# Cherry-MX-Testboard.net
KiCad netlist of a schematic drawn in EAGLE
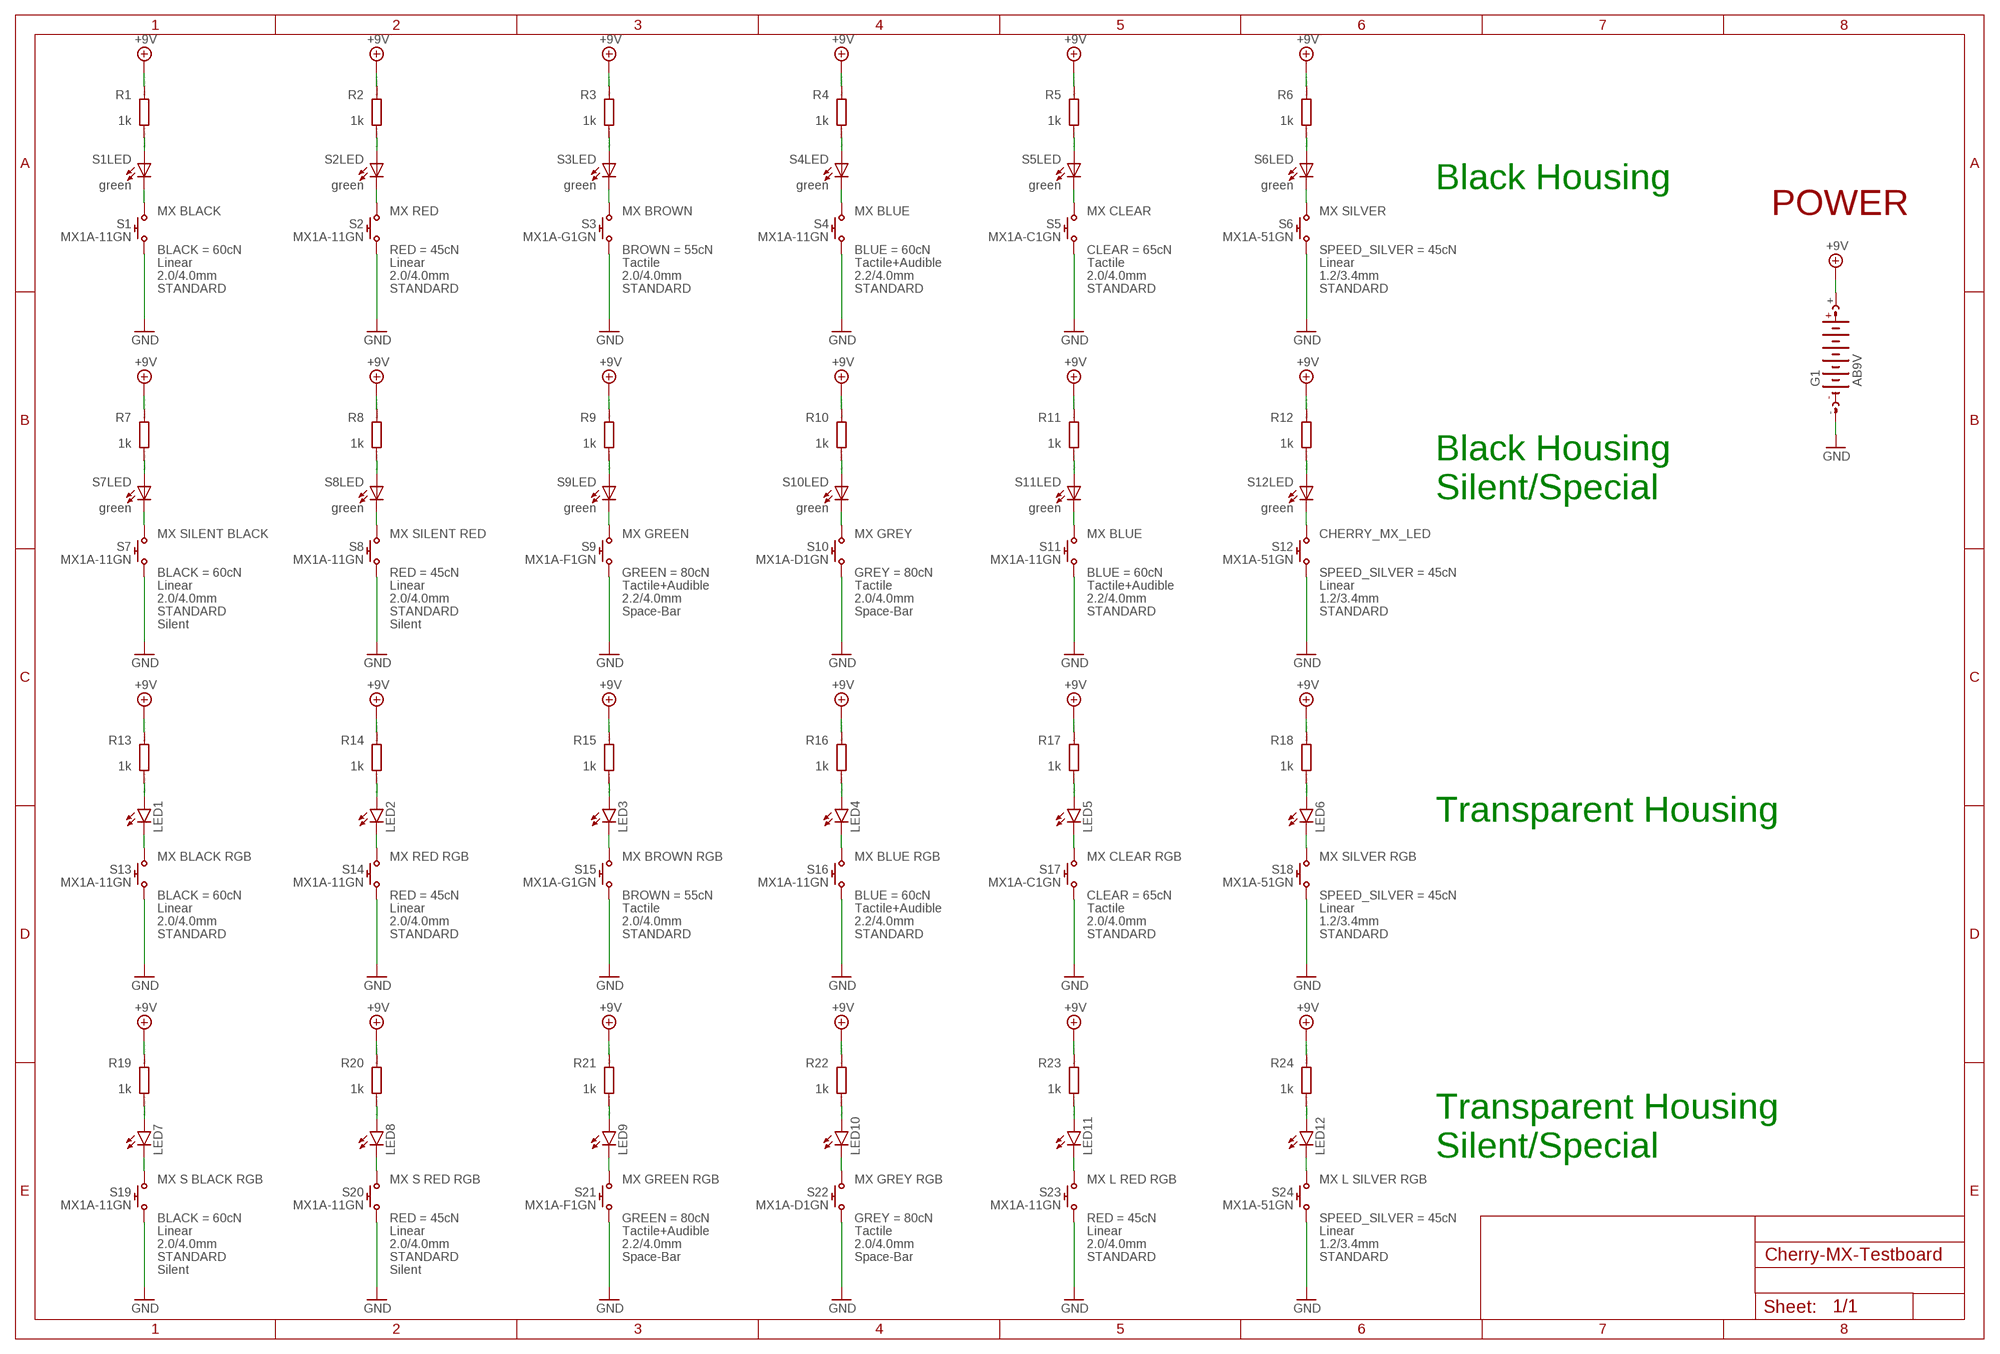
[diagram p0: schematic, sheet 1]

(export (version "E")
  (design (tool "Eeschema 10.0.6"))
  (components
    (comp (ref "G1")
      (value "AB9V")
      (footprint "eagle-import:AB9V")
      (libsource (lib "eagle-import") (part "AB9V"))
    )
    (comp (ref "LED1")
      (value "LEDMINI-TOP")
      (footprint "eagle-import:OSRAM-MINI-TOP-LED")
      (libsource (lib "eagle-import") (part "LEDMINI-TOP"))
    )
    (comp (ref "LED2")
      (value "LEDMINI-TOP")
      (footprint "eagle-import:OSRAM-MINI-TOP-LED")
      (libsource (lib "eagle-import") (part "LEDMINI-TOP"))
    )
    (comp (ref "LED3")
      (value "LEDMINI-TOP")
      (footprint "eagle-import:OSRAM-MINI-TOP-LED")
      (libsource (lib "eagle-import") (part "LEDMINI-TOP"))
    )
    (comp (ref "LED4")
      (value "LEDMINI-TOP")
      (footprint "eagle-import:OSRAM-MINI-TOP-LED")
      (libsource (lib "eagle-import") (part "LEDMINI-TOP"))
    )
    (comp (ref "LED5")
      (value "LEDMINI-TOP")
      (footprint "eagle-import:OSRAM-MINI-TOP-LED")
      (libsource (lib "eagle-import") (part "LEDMINI-TOP"))
    )
    (comp (ref "LED6")
      (value "LEDMINI-TOP")
      (footprint "eagle-import:OSRAM-MINI-TOP-LED")
      (libsource (lib "eagle-import") (part "LEDMINI-TOP"))
    )
    (comp (ref "LED7")
      (value "LEDMINI-TOP")
      (footprint "eagle-import:OSRAM-MINI-TOP-LED")
      (libsource (lib "eagle-import") (part "LEDMINI-TOP"))
    )
    (comp (ref "LED8")
      (value "LEDMINI-TOP")
      (footprint "eagle-import:OSRAM-MINI-TOP-LED")
      (libsource (lib "eagle-import") (part "LEDMINI-TOP"))
    )
    (comp (ref "LED9")
      (value "LEDMINI-TOP")
      (footprint "eagle-import:OSRAM-MINI-TOP-LED")
      (libsource (lib "eagle-import") (part "LEDMINI-TOP"))
    )
    (comp (ref "LED10")
      (value "LEDMINI-TOP")
      (footprint "eagle-import:OSRAM-MINI-TOP-LED")
      (libsource (lib "eagle-import") (part "LEDMINI-TOP"))
    )
    (comp (ref "LED11")
      (value "LEDMINI-TOP")
      (footprint "eagle-import:OSRAM-MINI-TOP-LED")
      (libsource (lib "eagle-import") (part "LEDMINI-TOP"))
    )
    (comp (ref "LED12")
      (value "LEDMINI-TOP")
      (footprint "eagle-import:OSRAM-MINI-TOP-LED")
      (libsource (lib "eagle-import") (part "LEDMINI-TOP"))
    )
    (comp (ref "R1")
      (value "1k")
      (footprint "eagle-import:R0402")
      (libsource (lib "eagle-import") (part "RR0402"))
    )
    (comp (ref "R2")
      (value "1k")
      (footprint "eagle-import:R0402")
      (libsource (lib "eagle-import") (part "RR0402"))
    )
    (comp (ref "R3")
      (value "1k")
      (footprint "eagle-import:R0402")
      (libsource (lib "eagle-import") (part "RR0402"))
    )
    (comp (ref "R4")
      (value "1k")
      (footprint "eagle-import:R0402")
      (libsource (lib "eagle-import") (part "RR0402"))
    )
    (comp (ref "R5")
      (value "1k")
      (footprint "eagle-import:R0402")
      (libsource (lib "eagle-import") (part "RR0402"))
    )
    (comp (ref "R6")
      (value "1k")
      (footprint "eagle-import:R0402")
      (libsource (lib "eagle-import") (part "RR0402"))
    )
    (comp (ref "R7")
      (value "1k")
      (footprint "eagle-import:R0402")
      (libsource (lib "eagle-import") (part "RR0402"))
    )
    (comp (ref "R8")
      (value "1k")
      (footprint "eagle-import:R0402")
      (libsource (lib "eagle-import") (part "RR0402"))
    )
    (comp (ref "R9")
      (value "1k")
      (footprint "eagle-import:R0402")
      (libsource (lib "eagle-import") (part "RR0402"))
    )
    (comp (ref "R10")
      (value "1k")
      (footprint "eagle-import:R0402")
      (libsource (lib "eagle-import") (part "RR0402"))
    )
    (comp (ref "R11")
      (value "1k")
      (footprint "eagle-import:R0402")
      (libsource (lib "eagle-import") (part "RR0402"))
    )
    (comp (ref "R12")
      (value "1k")
      (footprint "eagle-import:R0402")
      (libsource (lib "eagle-import") (part "RR0402"))
    )
    (comp (ref "R13")
      (value "1k")
      (footprint "eagle-import:R0402")
      (libsource (lib "eagle-import") (part "RR0402"))
    )
    (comp (ref "R14")
      (value "1k")
      (footprint "eagle-import:R0402")
      (libsource (lib "eagle-import") (part "RR0402"))
    )
    (comp (ref "R15")
      (value "1k")
      (footprint "eagle-import:R0402")
      (libsource (lib "eagle-import") (part "RR0402"))
    )
    (comp (ref "R16")
      (value "1k")
      (footprint "eagle-import:R0402")
      (libsource (lib "eagle-import") (part "RR0402"))
    )
    (comp (ref "R17")
      (value "1k")
      (footprint "eagle-import:R0402")
      (libsource (lib "eagle-import") (part "RR0402"))
    )
    (comp (ref "R18")
      (value "1k")
      (footprint "eagle-import:R0402")
      (libsource (lib "eagle-import") (part "RR0402"))
    )
    (comp (ref "R19")
      (value "1k")
      (footprint "eagle-import:R0402")
      (libsource (lib "eagle-import") (part "RR0402"))
    )
    (comp (ref "R20")
      (value "1k")
      (footprint "eagle-import:R0402")
      (libsource (lib "eagle-import") (part "RR0402"))
    )
    (comp (ref "R21")
      (value "1k")
      (footprint "eagle-import:R0402")
      (libsource (lib "eagle-import") (part "RR0402"))
    )
    (comp (ref "R22")
      (value "1k")
      (footprint "eagle-import:R0402")
      (libsource (lib "eagle-import") (part "RR0402"))
    )
    (comp (ref "R23")
      (value "1k")
      (footprint "eagle-import:R0402")
      (libsource (lib "eagle-import") (part "RR0402"))
    )
    (comp (ref "R24")
      (value "1k")
      (footprint "eagle-import:R0402")
      (libsource (lib "eagle-import") (part "RR0402"))
    )
    (comp (ref "S1")
      (value "MX BLACK")
      (footprint "eagle-import:CHERRY_MX_LED")
      (fields
        (field (name "BLACK") "60cN")
        (field (name "CHARACTERISTICS") "Linear")
        (field (name "CODE") "MX1A-11GN")
        (field (name "COLOR") "green")
        (field (name "FEATURE") "STANDARD")
        (field (name "TRAVEL") "2.0/4.0mm")
      )
      (libsource (lib "eagle-import") (part "CHERRY_MX_LED"))
    )
    (comp (ref "S2")
      (value "MX RED")
      (footprint "eagle-import:CHERRY_MX_LED")
      (fields
        (field (name "CHARACTERISTICS") "Linear")
        (field (name "CODE") "MX1A-11GN")
        (field (name "COLOR") "green")
        (field (name "FEATURE") "STANDARD")
        (field (name "RED") "45cN")
        (field (name "TRAVEL") "2.0/4.0mm")
      )
      (libsource (lib "eagle-import") (part "CHERRY_MX_LED"))
    )
    (comp (ref "S3")
      (value "MX BROWN")
      (footprint "eagle-import:CHERRY_MX_LED")
      (fields
        (field (name "BROWN") "55cN")
        (field (name "CHARACTERISTICS") "Tactile")
        (field (name "CODE") "MX1A-G1GN")
        (field (name "COLOR") "green")
        (field (name "FEATURE") "STANDARD")
        (field (name "TRAVEL") "2.0/4.0mm")
      )
      (libsource (lib "eagle-import") (part "CHERRY_MX_LED"))
    )
    (comp (ref "S4")
      (value "MX BLUE")
      (footprint "eagle-import:CHERRY_MX_LED")
      (fields
        (field (name "BLUE") "60cN")
        (field (name "CHARACTERISTICS") "Tactile+Audible")
        (field (name "CODE") "MX1A-11GN")
        (field (name "COLOR") "green")
        (field (name "FEATURE") "STANDARD")
        (field (name "MOUSER") "540_MX1A_E1NW")
        (field (name "TRAVEL") "2.2/4.0mm")
      )
      (libsource (lib "eagle-import") (part "CHERRY_MX_LED"))
    )
    (comp (ref "S5")
      (value "MX CLEAR")
      (footprint "eagle-import:CHERRY_MX_LED")
      (fields
        (field (name "CHARACTERISTICS") "Tactile")
        (field (name "CLEAR") "65cN")
        (field (name "CODE") "MX1A-C1GN")
        (field (name "COLOR") "green")
        (field (name "FEATURE") "STANDARD")
        (field (name "TRAVEL") "2.0/4.0mm")
      )
      (libsource (lib "eagle-import") (part "CHERRY_MX_LED"))
    )
    (comp (ref "S6")
      (value "MX SILVER")
      (footprint "eagle-import:CHERRY_MX_LED")
      (fields
        (field (name "CHARACTERISTICS") "Linear")
        (field (name "CODE") "MX1A-51GN")
        (field (name "COLOR") "green")
        (field (name "FEATURE") "STANDARD")
        (field (name "SPEED_SILVER") "45cN")
        (field (name "TRAVEL") "1.2/3.4mm")
      )
      (libsource (lib "eagle-import") (part "CHERRY_MX_LED"))
    )
    (comp (ref "S7")
      (value "MX SILENT BLACK")
      (footprint "eagle-import:CHERRY_MX_LED")
      (fields
        (field (name "BLACK") "60cN")
        (field (name "CHARACTERISTICS") "Linear")
        (field (name "CODE") "MX1A-11GN")
        (field (name "COLOR") "green")
        (field (name "FEATURE") "STANDARD")
        (field (name "NOISE") "Silent")
        (field (name "TRAVEL") "2.0/4.0mm")
      )
      (libsource (lib "eagle-import") (part "CHERRY_MX_LED"))
    )
    (comp (ref "S8")
      (value "MX SILENT RED")
      (footprint "eagle-import:CHERRY_MX_LED")
      (fields
        (field (name "CHARACTERISTICS") "Linear")
        (field (name "CODE") "MX1A-11GN")
        (field (name "COLOR") "green")
        (field (name "FEATURE") "STANDARD")
        (field (name "NOISE") "Silent")
        (field (name "RED") "45cN")
        (field (name "TRAVEL") "2.0/4.0mm")
      )
      (libsource (lib "eagle-import") (part "CHERRY_MX_LED"))
    )
    (comp (ref "S9")
      (value "MX GREEN")
      (footprint "eagle-import:CHERRY_MX_LED")
      (fields
        (field (name "CHARACTERISTICS") "Tactile+Audible")
        (field (name "CODE") "MX1A-F1GN")
        (field (name "COLOR") "green")
        (field (name "FEATURE") "Space-Bar")
        (field (name "GREEN") "80cN")
        (field (name "TRAVEL") "2.2/4.0mm")
      )
      (libsource (lib "eagle-import") (part "CHERRY_MX_LED"))
    )
    (comp (ref "S10")
      (value "MX GREY")
      (footprint "eagle-import:CHERRY_MX_LED")
      (fields
        (field (name "CHARACTERISTICS") "Tactile")
        (field (name "CODE") "MX1A-D1GN")
        (field (name "COLOR") "green")
        (field (name "FEATURE") "Space-Bar")
        (field (name "GREY") "80cN")
        (field (name "MOUSER") "540_MX1A_21NW")
        (field (name "TRAVEL") "2.0/4.0mm")
      )
      (libsource (lib "eagle-import") (part "CHERRY_MX_LED"))
    )
    (comp (ref "S11")
      (value "MX BLUE")
      (footprint "eagle-import:CHERRY_MX_LED")
      (fields
        (field (name "BLUE") "60cN")
        (field (name "CHARACTERISTICS") "Tactile+Audible")
        (field (name "CODE") "MX1A-11GN")
        (field (name "COLOR") "green")
        (field (name "FEATURE") "STANDARD")
        (field (name "MOUSER") "540_MX1A_E1NW")
        (field (name "TRAVEL") "2.2/4.0mm")
      )
      (libsource (lib "eagle-import") (part "CHERRY_MX_LED"))
    )
    (comp (ref "S12")
      (value "CHERRY_MX_LED")
      (footprint "eagle-import:CHERRY_MX_LED")
      (fields
        (field (name "CHARACTERISTICS") "Linear")
        (field (name "CODE") "MX1A-51GN")
        (field (name "COLOR") "green")
        (field (name "FEATURE") "STANDARD")
        (field (name "SPEED_SILVER") "45cN")
        (field (name "TRAVEL") "1.2/3.4mm")
      )
      (libsource (lib "eagle-import") (part "CHERRY_MX_LED"))
    )
    (comp (ref "S13")
      (value "MX BLACK RGB")
      (footprint "eagle-import:CHERRY_MX")
      (fields
        (field (name "BLACK") "60cN")
        (field (name "CHARACTERISTICS") "Linear")
        (field (name "CODE") "MX1A-11GN")
        (field (name "COLOR") "green")
        (field (name "FEATURE") "STANDARD")
        (field (name "TRAVEL") "2.0/4.0mm")
      )
      (libsource (lib "eagle-import") (part "CHERRY_MX"))
    )
    (comp (ref "S14")
      (value "MX RED RGB")
      (footprint "eagle-import:CHERRY_MX")
      (fields
        (field (name "CHARACTERISTICS") "Linear")
        (field (name "CODE") "MX1A-11GN")
        (field (name "COLOR") "green")
        (field (name "FEATURE") "STANDARD")
        (field (name "RED") "45cN")
        (field (name "TRAVEL") "2.0/4.0mm")
      )
      (libsource (lib "eagle-import") (part "CHERRY_MX"))
    )
    (comp (ref "S15")
      (value "MX BROWN RGB")
      (footprint "eagle-import:CHERRY_MX")
      (fields
        (field (name "BROWN") "55cN")
        (field (name "CHARACTERISTICS") "Tactile")
        (field (name "CODE") "MX1A-G1GN")
        (field (name "COLOR") "green")
        (field (name "FEATURE") "STANDARD")
        (field (name "TRAVEL") "2.0/4.0mm")
      )
      (libsource (lib "eagle-import") (part "CHERRY_MX"))
    )
    (comp (ref "S16")
      (value "MX BLUE RGB")
      (footprint "eagle-import:CHERRY_MX")
      (fields
        (field (name "BLUE") "60cN")
        (field (name "CHARACTERISTICS") "Tactile+Audible")
        (field (name "CODE") "MX1A-11GN")
        (field (name "COLOR") "green")
        (field (name "FEATURE") "STANDARD")
        (field (name "TRAVEL") "2.2/4.0mm")
      )
      (libsource (lib "eagle-import") (part "CHERRY_MX"))
    )
    (comp (ref "S17")
      (value "MX CLEAR RGB")
      (footprint "eagle-import:CHERRY_MX")
      (fields
        (field (name "CHARACTERISTICS") "Tactile")
        (field (name "CLEAR") "65cN")
        (field (name "CODE") "MX1A-C1GN")
        (field (name "COLOR") "green")
        (field (name "FEATURE") "STANDARD")
        (field (name "TRAVEL") "2.0/4.0mm")
      )
      (libsource (lib "eagle-import") (part "CHERRY_MX"))
    )
    (comp (ref "S18")
      (value "MX SILVER RGB")
      (footprint "eagle-import:CHERRY_MX")
      (fields
        (field (name "CHARACTERISTICS") "Linear")
        (field (name "CODE") "MX1A-51GN")
        (field (name "COLOR") "green")
        (field (name "FEATURE") "STANDARD")
        (field (name "SPEED_SILVER") "45cN")
        (field (name "TRAVEL") "1.2/3.4mm")
      )
      (libsource (lib "eagle-import") (part "CHERRY_MX"))
    )
    (comp (ref "S19")
      (value "MX S BLACK RGB")
      (footprint "eagle-import:CHERRY_MX")
      (fields
        (field (name "BLACK") "60cN")
        (field (name "CHARACTERISTICS") "Linear")
        (field (name "CODE") "MX1A-11GN")
        (field (name "COLOR") "green")
        (field (name "FEATURE") "STANDARD")
        (field (name "NOISE") "Silent")
        (field (name "TRAVEL") "2.0/4.0mm")
      )
      (libsource (lib "eagle-import") (part "CHERRY_MX"))
    )
    (comp (ref "S20")
      (value "MX S RED RGB")
      (footprint "eagle-import:CHERRY_MX")
      (fields
        (field (name "CHARACTERISTICS") "Linear")
        (field (name "CODE") "MX1A-11GN")
        (field (name "COLOR") "green")
        (field (name "FEATURE") "STANDARD")
        (field (name "NOISE") "Silent")
        (field (name "RED") "45cN")
        (field (name "TRAVEL") "2.0/4.0mm")
      )
      (libsource (lib "eagle-import") (part "CHERRY_MX"))
    )
    (comp (ref "S21")
      (value "MX GREEN RGB")
      (footprint "eagle-import:CHERRY_MX")
      (fields
        (field (name "CHARACTERISTICS") "Tactile+Audible")
        (field (name "CODE") "MX1A-F1GN")
        (field (name "COLOR") "green")
        (field (name "FEATURE") "Space-Bar")
        (field (name "GREEN") "80cN")
        (field (name "TRAVEL") "2.2/4.0mm")
      )
      (libsource (lib "eagle-import") (part "CHERRY_MX"))
    )
    (comp (ref "S22")
      (value "MX GREY RGB")
      (footprint "eagle-import:CHERRY_MX")
      (fields
        (field (name "CHARACTERISTICS") "Tactile")
        (field (name "CODE") "MX1A-D1GN")
        (field (name "COLOR") "green")
        (field (name "FEATURE") "Space-Bar")
        (field (name "GREY") "80cN")
        (field (name "TRAVEL") "2.0/4.0mm")
      )
      (libsource (lib "eagle-import") (part "CHERRY_MX"))
    )
    (comp (ref "S23")
      (value "MX L RED RGB")
      (footprint "eagle-import:CHERRY_MX")
      (fields
        (field (name "CHARACTERISTICS") "Linear")
        (field (name "CODE") "MX1A-11GN")
        (field (name "COLOR") "green")
        (field (name "FEATURE") "STANDARD")
        (field (name "RED") "45cN")
        (field (name "TRAVEL") "2.0/4.0mm")
      )
      (libsource (lib "eagle-import") (part "CHERRY_MX"))
    )
    (comp (ref "S24")
      (value "MX L SILVER RGB")
      (footprint "eagle-import:CHERRY_MX")
      (fields
        (field (name "CHARACTERISTICS") "Linear")
        (field (name "CODE") "MX1A-51GN")
        (field (name "COLOR") "green")
        (field (name "FEATURE") "STANDARD")
        (field (name "SPEED_SILVER") "45cN")
        (field (name "TRAVEL") "1.2/3.4mm")
      )
      (libsource (lib "eagle-import") (part "CHERRY_MX"))
    )
  )
  (nets
    (net (code "1") (name "+9V") (class "Default")
      (node (ref "G1") (pin "+") (pinfunction "+_+") (pintype "passive"))
      (node (ref "R1") (pin "1") (pinfunction "1_1") (pintype "passive"))
      (node (ref "R10") (pin "1") (pinfunction "1_1") (pintype "passive"))
      (node (ref "R11") (pin "1") (pinfunction "1_1") (pintype "passive"))
      (node (ref "R12") (pin "1") (pinfunction "1_1") (pintype "passive"))
      (node (ref "R13") (pin "1") (pinfunction "1_1") (pintype "passive"))
      (node (ref "R14") (pin "1") (pinfunction "1_1") (pintype "passive"))
      (node (ref "R15") (pin "1") (pinfunction "1_1") (pintype "passive"))
      (node (ref "R16") (pin "1") (pinfunction "1_1") (pintype "passive"))
      (node (ref "R17") (pin "1") (pinfunction "1_1") (pintype "passive"))
      (node (ref "R18") (pin "1") (pinfunction "1_1") (pintype "passive"))
      (node (ref "R19") (pin "1") (pinfunction "1_1") (pintype "passive"))
      (node (ref "R2") (pin "1") (pinfunction "1_1") (pintype "passive"))
      (node (ref "R20") (pin "1") (pinfunction "1_1") (pintype "passive"))
      (node (ref "R21") (pin "1") (pinfunction "1_1") (pintype "passive"))
      (node (ref "R22") (pin "1") (pinfunction "1_1") (pintype "passive"))
      (node (ref "R23") (pin "1") (pinfunction "1_1") (pintype "passive"))
      (node (ref "R24") (pin "1") (pinfunction "1_1") (pintype "passive"))
      (node (ref "R3") (pin "1") (pinfunction "1_1") (pintype "passive"))
      (node (ref "R4") (pin "1") (pinfunction "1_1") (pintype "passive"))
      (node (ref "R5") (pin "1") (pinfunction "1_1") (pintype "passive"))
      (node (ref "R6") (pin "1") (pinfunction "1_1") (pintype "passive"))
      (node (ref "R7") (pin "1") (pinfunction "1_1") (pintype "passive"))
      (node (ref "R8") (pin "1") (pinfunction "1_1") (pintype "passive"))
      (node (ref "R9") (pin "1") (pinfunction "1_1") (pintype "passive"))
    )
    (net (code "2") (name "GND") (class "Default")
      (node (ref "G1") (pin "-") (pinfunction "-_-") (pintype "passive"))
      (node (ref "S1") (pin "S1") (pinfunction "1_S1") (pintype "passive"))
      (node (ref "S10") (pin "S1") (pinfunction "1_S1") (pintype "passive"))
      (node (ref "S11") (pin "S1") (pinfunction "1_S1") (pintype "passive"))
      (node (ref "S12") (pin "S1") (pinfunction "1_S1") (pintype "passive"))
      (node (ref "S13") (pin "S1") (pinfunction "1_S1") (pintype "passive"))
      (node (ref "S14") (pin "S1") (pinfunction "1_S1") (pintype "passive"))
      (node (ref "S15") (pin "S1") (pinfunction "1_S1") (pintype "passive"))
      (node (ref "S16") (pin "S1") (pinfunction "1_S1") (pintype "passive"))
      (node (ref "S17") (pin "S1") (pinfunction "1_S1") (pintype "passive"))
      (node (ref "S18") (pin "S1") (pinfunction "1_S1") (pintype "passive"))
      (node (ref "S19") (pin "S1") (pinfunction "1_S1") (pintype "passive"))
      (node (ref "S2") (pin "S1") (pinfunction "1_S1") (pintype "passive"))
      (node (ref "S20") (pin "S1") (pinfunction "1_S1") (pintype "passive"))
      (node (ref "S21") (pin "S1") (pinfunction "1_S1") (pintype "passive"))
      (node (ref "S22") (pin "S1") (pinfunction "1_S1") (pintype "passive"))
      (node (ref "S23") (pin "S1") (pinfunction "1_S1") (pintype "passive"))
      (node (ref "S24") (pin "S1") (pinfunction "1_S1") (pintype "passive"))
      (node (ref "S3") (pin "S1") (pinfunction "1_S1") (pintype "passive"))
      (node (ref "S4") (pin "S1") (pinfunction "1_S1") (pintype "passive"))
      (node (ref "S5") (pin "S1") (pinfunction "1_S1") (pintype "passive"))
      (node (ref "S6") (pin "S1") (pinfunction "1_S1") (pintype "passive"))
      (node (ref "S7") (pin "S1") (pinfunction "1_S1") (pintype "passive"))
      (node (ref "S8") (pin "S1") (pinfunction "1_S1") (pintype "passive"))
      (node (ref "S9") (pin "S1") (pinfunction "1_S1") (pintype "passive"))
    )
    (net (code "3") (name "Net-(LED1-PadA)") (class "Default")
      (node (ref "LED1") (pin "A") (pinfunction "A_A") (pintype "passive"))
      (node (ref "R13") (pin "2") (pinfunction "2_2") (pintype "passive"))
    )
    (net (code "4") (name "Net-(LED2-PadA)") (class "Default")
      (node (ref "LED2") (pin "A") (pinfunction "A_A") (pintype "passive"))
      (node (ref "R14") (pin "2") (pinfunction "2_2") (pintype "passive"))
    )
    (net (code "5") (name "Net-(LED3-PadA)") (class "Default")
      (node (ref "LED3") (pin "A") (pinfunction "A_A") (pintype "passive"))
      (node (ref "R15") (pin "2") (pinfunction "2_2") (pintype "passive"))
    )
    (net (code "6") (name "Net-(LED4-PadA)") (class "Default")
      (node (ref "LED4") (pin "A") (pinfunction "A_A") (pintype "passive"))
      (node (ref "R16") (pin "2") (pinfunction "2_2") (pintype "passive"))
    )
    (net (code "7") (name "Net-(LED5-PadA)") (class "Default")
      (node (ref "LED5") (pin "A") (pinfunction "A_A") (pintype "passive"))
      (node (ref "R17") (pin "2") (pinfunction "2_2") (pintype "passive"))
    )
    (net (code "8") (name "Net-(LED6-PadA)") (class "Default")
      (node (ref "LED6") (pin "A") (pinfunction "A_A") (pintype "passive"))
      (node (ref "R18") (pin "2") (pinfunction "2_2") (pintype "passive"))
    )
    (net (code "9") (name "Net-(LED7-PadA)") (class "Default")
      (node (ref "LED7") (pin "A") (pinfunction "A_A") (pintype "passive"))
      (node (ref "R19") (pin "2") (pinfunction "2_2") (pintype "passive"))
    )
    (net (code "10") (name "Net-(LED8-PadA)") (class "Default")
      (node (ref "LED8") (pin "A") (pinfunction "A_A") (pintype "passive"))
      (node (ref "R20") (pin "2") (pinfunction "2_2") (pintype "passive"))
    )
    (net (code "11") (name "Net-(LED9-PadA)") (class "Default")
      (node (ref "LED9") (pin "A") (pinfunction "A_A") (pintype "passive"))
      (node (ref "R21") (pin "2") (pinfunction "2_2") (pintype "passive"))
    )
    (net (code "12") (name "Net-(LED10-PadA)") (class "Default")
      (node (ref "LED10") (pin "A") (pinfunction "A_A") (pintype "passive"))
      (node (ref "R22") (pin "2") (pinfunction "2_2") (pintype "passive"))
    )
    (net (code "13") (name "Net-(LED11-PadA)") (class "Default")
      (node (ref "LED11") (pin "A") (pinfunction "A_A") (pintype "passive"))
      (node (ref "R23") (pin "2") (pinfunction "2_2") (pintype "passive"))
    )
    (net (code "14") (name "Net-(LED12-PadA)") (class "Default")
      (node (ref "LED12") (pin "A") (pinfunction "A_A") (pintype "passive"))
      (node (ref "R24") (pin "2") (pinfunction "2_2") (pintype "passive"))
    )
    (net (code "15") (name "Net-(S1A-2)") (class "Default")
      (node (ref "S1") (pin "L2") (pinfunction "C_L2") (pintype "passive"))
      (node (ref "S1") (pin "S2") (pinfunction "2_S2") (pintype "passive"))
    )
    (net (code "16") (name "Net-(S1B-A)") (class "Default")
      (node (ref "R1") (pin "2") (pinfunction "2_2") (pintype "passive"))
      (node (ref "S1") (pin "L1") (pinfunction "A_L1") (pintype "passive"))
    )
    (net (code "17") (name "Net-(S2A-2)") (class "Default")
      (node (ref "S2") (pin "L2") (pinfunction "C_L2") (pintype "passive"))
      (node (ref "S2") (pin "S2") (pinfunction "2_S2") (pintype "passive"))
    )
    (net (code "18") (name "Net-(S2B-A)") (class "Default")
      (node (ref "R2") (pin "2") (pinfunction "2_2") (pintype "passive"))
      (node (ref "S2") (pin "L1") (pinfunction "A_L1") (pintype "passive"))
    )
    (net (code "19") (name "Net-(S3A-2)") (class "Default")
      (node (ref "S3") (pin "L2") (pinfunction "C_L2") (pintype "passive"))
      (node (ref "S3") (pin "S2") (pinfunction "2_S2") (pintype "passive"))
    )
    (net (code "20") (name "Net-(S3B-A)") (class "Default")
      (node (ref "R3") (pin "2") (pinfunction "2_2") (pintype "passive"))
      (node (ref "S3") (pin "L1") (pinfunction "A_L1") (pintype "passive"))
    )
    (net (code "21") (name "Net-(S4A-2)") (class "Default")
      (node (ref "S4") (pin "L2") (pinfunction "C_L2") (pintype "passive"))
      (node (ref "S4") (pin "S2") (pinfunction "2_S2") (pintype "passive"))
    )
    (net (code "22") (name "Net-(S4B-A)") (class "Default")
      (node (ref "R4") (pin "2") (pinfunction "2_2") (pintype "passive"))
      (node (ref "S4") (pin "L1") (pinfunction "A_L1") (pintype "passive"))
    )
    (net (code "23") (name "Net-(S5A-2)") (class "Default")
      (node (ref "S5") (pin "L2") (pinfunction "C_L2") (pintype "passive"))
      (node (ref "S5") (pin "S2") (pinfunction "2_S2") (pintype "passive"))
    )
    (net (code "24") (name "Net-(S5B-A)") (class "Default")
      (node (ref "R5") (pin "2") (pinfunction "2_2") (pintype "passive"))
      (node (ref "S5") (pin "L1") (pinfunction "A_L1") (pintype "passive"))
    )
    (net (code "25") (name "Net-(S6A-2)") (class "Default")
      (node (ref "S6") (pin "L2") (pinfunction "C_L2") (pintype "passive"))
      (node (ref "S6") (pin "S2") (pinfunction "2_S2") (pintype "passive"))
    )
    (net (code "26") (name "Net-(S6B-A)") (class "Default")
      (node (ref "R6") (pin "2") (pinfunction "2_2") (pintype "passive"))
      (node (ref "S6") (pin "L1") (pinfunction "A_L1") (pintype "passive"))
    )
    (net (code "27") (name "Net-(S7A-2)") (class "Default")
      (node (ref "S7") (pin "L2") (pinfunction "C_L2") (pintype "passive"))
      (node (ref "S7") (pin "S2") (pinfunction "2_S2") (pintype "passive"))
    )
    (net (code "28") (name "Net-(S7B-A)") (class "Default")
      (node (ref "R7") (pin "2") (pinfunction "2_2") (pintype "passive"))
      (node (ref "S7") (pin "L1") (pinfunction "A_L1") (pintype "passive"))
    )
    (net (code "29") (name "Net-(S8A-2)") (class "Default")
      (node (ref "S8") (pin "L2") (pinfunction "C_L2") (pintype "passive"))
      (node (ref "S8") (pin "S2") (pinfunction "2_S2") (pintype "passive"))
    )
    (net (code "30") (name "Net-(S8B-A)") (class "Default")
      (node (ref "R8") (pin "2") (pinfunction "2_2") (pintype "passive"))
      (node (ref "S8") (pin "L1") (pinfunction "A_L1") (pintype "passive"))
    )
    (net (code "31") (name "Net-(S9A-2)") (class "Default")
      (node (ref "S9") (pin "L2") (pinfunction "C_L2") (pintype "passive"))
      (node (ref "S9") (pin "S2") (pinfunction "2_S2") (pintype "passive"))
    )
    (net (code "32") (name "Net-(S9B-A)") (class "Default")
      (node (ref "R9") (pin "2") (pinfunction "2_2") (pintype "passive"))
      (node (ref "S9") (pin "L1") (pinfunction "A_L1") (pintype "passive"))
    )
    (net (code "33") (name "Net-(S10A-2)") (class "Default")
      (node (ref "S10") (pin "L2") (pinfunction "C_L2") (pintype "passive"))
      (node (ref "S10") (pin "S2") (pinfunction "2_S2") (pintype "passive"))
    )
    (net (code "34") (name "Net-(S10B-A)") (class "Default")
      (node (ref "R10") (pin "2") (pinfunction "2_2") (pintype "passive"))
      (node (ref "S10") (pin "L1") (pinfunction "A_L1") (pintype "passive"))
    )
    (net (code "35") (name "Net-(S11A-2)") (class "Default")
      (node (ref "S11") (pin "L2") (pinfunction "C_L2") (pintype "passive"))
      (node (ref "S11") (pin "S2") (pinfunction "2_S2") (pintype "passive"))
    )
    (net (code "36") (name "Net-(S11B-A)") (class "Default")
      (node (ref "R11") (pin "2") (pinfunction "2_2") (pintype "passive"))
      (node (ref "S11") (pin "L1") (pinfunction "A_L1") (pintype "passive"))
    )
    (net (code "37") (name "Net-(S12A-2)") (class "Default")
      (node (ref "S12") (pin "L2") (pinfunction "C_L2") (pintype "passive"))
      (node (ref "S12") (pin "S2") (pinfunction "2_S2") (pintype "passive"))
    )
    (net (code "38") (name "Net-(S12B-A)") (class "Default")
      (node (ref "R12") (pin "2") (pinfunction "2_2") (pintype "passive"))
      (node (ref "S12") (pin "L1") (pinfunction "A_L1") (pintype "passive"))
    )
    (net (code "39") (name "Net-(S13-2)") (class "Default")
      (node (ref "LED1") (pin "C") (pinfunction "C_C") (pintype "passive"))
      (node (ref "S13") (pin "S2") (pinfunction "2_S2") (pintype "passive"))
    )
    (net (code "40") (name "Net-(S14-2)") (class "Default")
      (node (ref "LED2") (pin "C") (pinfunction "C_C") (pintype "passive"))
      (node (ref "S14") (pin "S2") (pinfunction "2_S2") (pintype "passive"))
    )
    (net (code "41") (name "Net-(S15-2)") (class "Default")
      (node (ref "LED3") (pin "C") (pinfunction "C_C") (pintype "passive"))
      (node (ref "S15") (pin "S2") (pinfunction "2_S2") (pintype "passive"))
    )
    (net (code "42") (name "Net-(S16-2)") (class "Default")
      (node (ref "LED4") (pin "C") (pinfunction "C_C") (pintype "passive"))
      (node (ref "S16") (pin "S2") (pinfunction "2_S2") (pintype "passive"))
    )
    (net (code "43") (name "Net-(S17-2)") (class "Default")
      (node (ref "LED5") (pin "C") (pinfunction "C_C") (pintype "passive"))
      (node (ref "S17") (pin "S2") (pinfunction "2_S2") (pintype "passive"))
    )
    (net (code "44") (name "Net-(S18-2)") (class "Default")
      (node (ref "LED6") (pin "C") (pinfunction "C_C") (pintype "passive"))
      (node (ref "S18") (pin "S2") (pinfunction "2_S2") (pintype "passive"))
    )
    (net (code "45") (name "Net-(S19-2)") (class "Default")
      (node (ref "LED7") (pin "C") (pinfunction "C_C") (pintype "passive"))
      (node (ref "S19") (pin "S2") (pinfunction "2_S2") (pintype "passive"))
    )
    (net (code "46") (name "Net-(S20-2)") (class "Default")
      (node (ref "LED8") (pin "C") (pinfunction "C_C") (pintype "passive"))
      (node (ref "S20") (pin "S2") (pinfunction "2_S2") (pintype "passive"))
    )
    (net (code "47") (name "Net-(S21-2)") (class "Default")
      (node (ref "LED9") (pin "C") (pinfunction "C_C") (pintype "passive"))
      (node (ref "S21") (pin "S2") (pinfunction "2_S2") (pintype "passive"))
    )
    (net (code "48") (name "Net-(S22-2)") (class "Default")
      (node (ref "LED10") (pin "C") (pinfunction "C_C") (pintype "passive"))
      (node (ref "S22") (pin "S2") (pinfunction "2_S2") (pintype "passive"))
    )
    (net (code "49") (name "Net-(S23-2)") (class "Default")
      (node (ref "LED11") (pin "C") (pinfunction "C_C") (pintype "passive"))
      (node (ref "S23") (pin "S2") (pinfunction "2_S2") (pintype "passive"))
    )
    (net (code "50") (name "Net-(S24-2)") (class "Default")
      (node (ref "LED12") (pin "C") (pinfunction "C_C") (pintype "passive"))
      (node (ref "S24") (pin "S2") (pinfunction "2_S2") (pintype "passive"))
    )
  )
)
